# mother_card_09.net
KiCad netlist of a schematic drawn in EAGLE
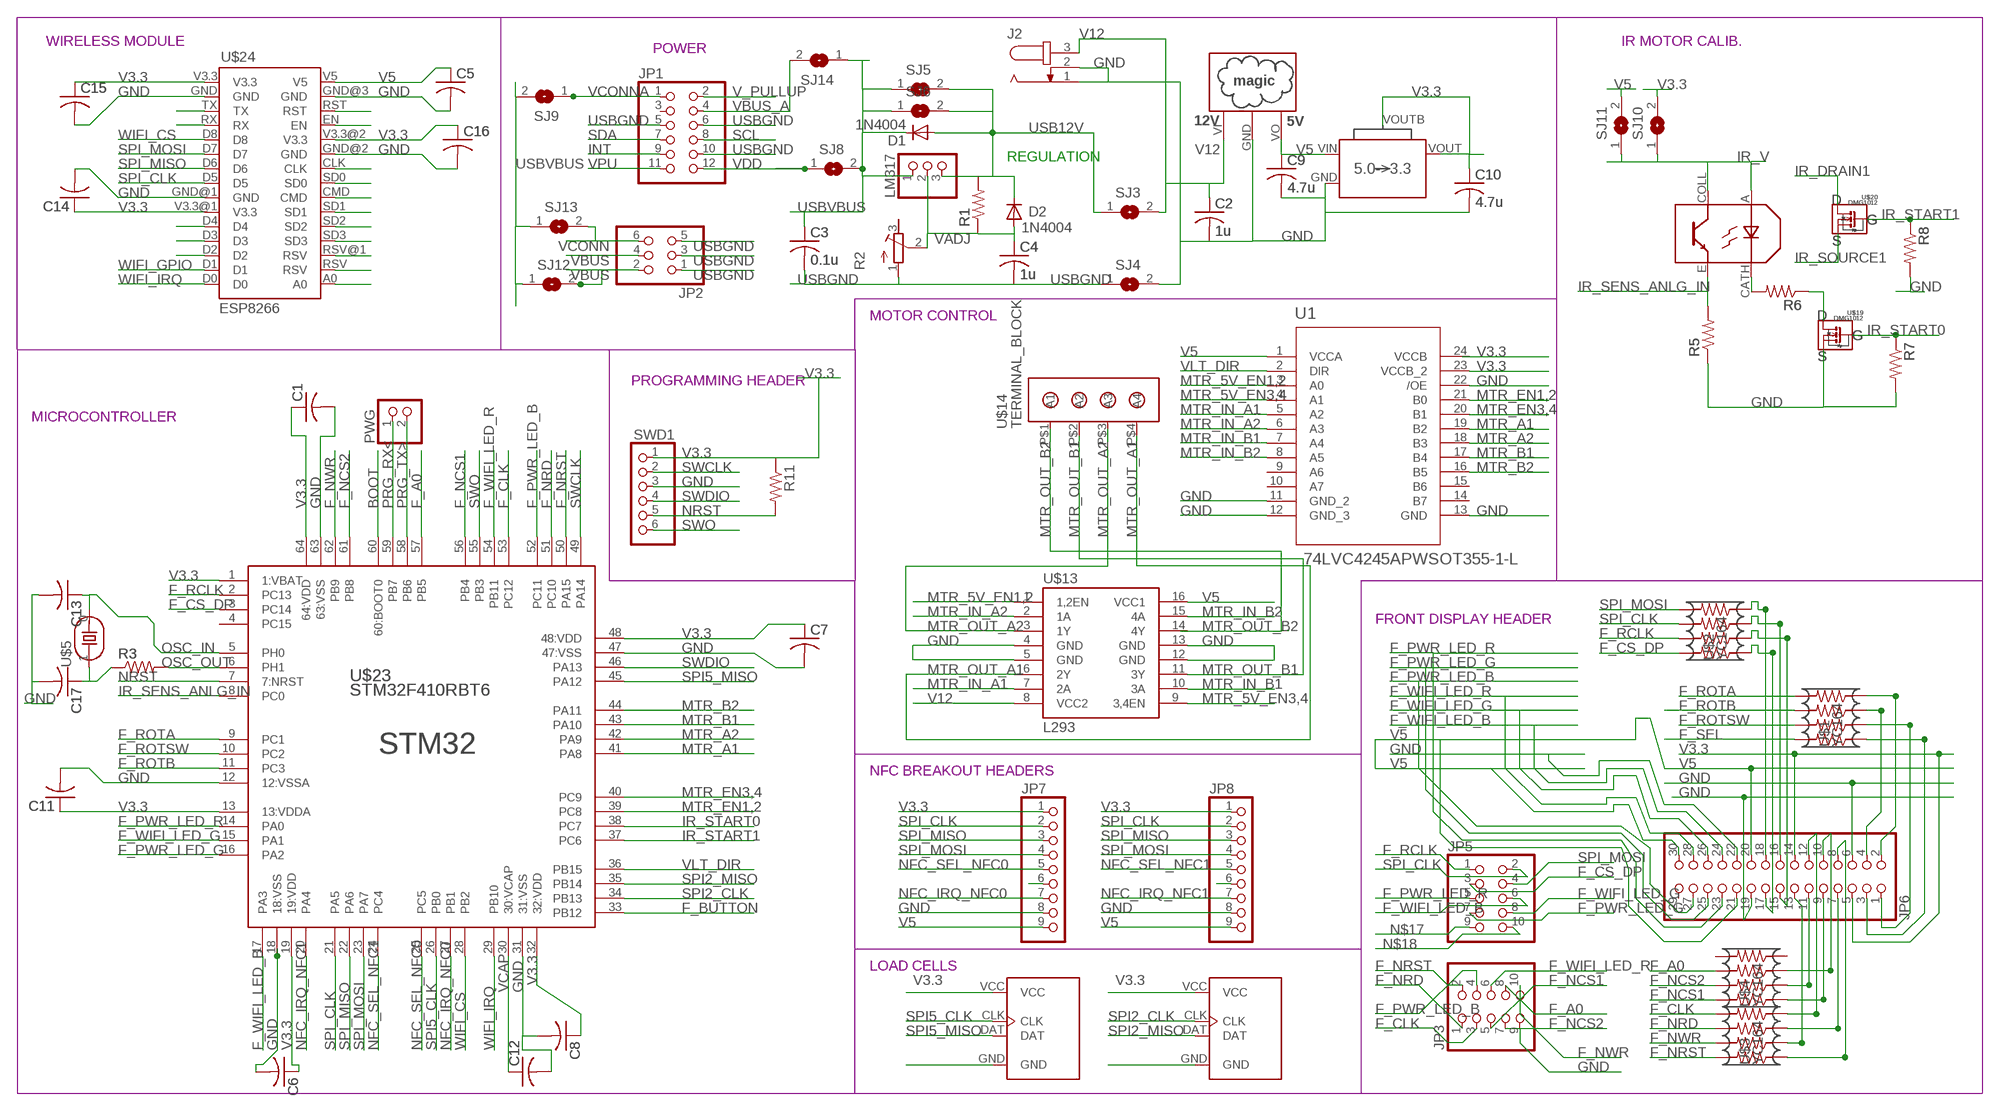
[diagram p0: schematic, sheet 1]

(export (version "E")
  (design (tool "Eeschema 10.0.6"))
  (components
    (comp (ref "C1")
      (value "C-USC0805")
      (footprint "eagle-import:C0805")
      (libsource (lib "eagle-import") (part "C-USC0805"))
    )
    (comp (ref "C2")
      (value "1u")
      (footprint "eagle-import:C0805")
      (libsource (lib "eagle-import") (part "C-USC0805"))
    )
    (comp (ref "C3")
      (value "0.1u")
      (footprint "eagle-import:C0805")
      (libsource (lib "eagle-import") (part "C-USC0805"))
    )
    (comp (ref "C4")
      (value "1u")
      (footprint "eagle-import:C0805")
      (libsource (lib "eagle-import") (part "C-USC0805"))
    )
    (comp (ref "C5")
      (value "C-USC0805")
      (footprint "eagle-import:C0805")
      (libsource (lib "eagle-import") (part "C-USC0805"))
    )
    (comp (ref "C6")
      (value "C-USC0805")
      (footprint "eagle-import:C0805")
      (libsource (lib "eagle-import") (part "C-USC0805"))
    )
    (comp (ref "C7")
      (value "C-USC0805")
      (footprint "eagle-import:C0805")
      (libsource (lib "eagle-import") (part "C-USC0805"))
    )
    (comp (ref "C8")
      (value "C-USC0805")
      (footprint "eagle-import:C0805")
      (libsource (lib "eagle-import") (part "C-USC0805"))
    )
    (comp (ref "C9")
      (value "4.7u")
      (footprint "eagle-import:C0805")
      (libsource (lib "eagle-import") (part "C-USC0805"))
    )
    (comp (ref "C10")
      (value "4.7u")
      (footprint "eagle-import:C0805")
      (libsource (lib "eagle-import") (part "C-USC0805"))
    )
    (comp (ref "C11")
      (value "C-USC0805")
      (footprint "eagle-import:C0805")
      (libsource (lib "eagle-import") (part "C-USC0805"))
    )
    (comp (ref "C12")
      (value "C-USC0805")
      (footprint "eagle-import:C0805")
      (libsource (lib "eagle-import") (part "C-USC0805"))
    )
    (comp (ref "C13")
      (value "C-USC0603")
      (footprint "eagle-import:C0603")
      (libsource (lib "eagle-import") (part "C-USC0603"))
    )
    (comp (ref "C14")
      (value "C-USC0805")
      (footprint "eagle-import:C0805")
      (libsource (lib "eagle-import") (part "C-USC0805"))
    )
    (comp (ref "C15")
      (value "C-USC0805")
      (footprint "eagle-import:C0805")
      (libsource (lib "eagle-import") (part "C-USC0805"))
    )
    (comp (ref "C16")
      (value "C-USC0805")
      (footprint "eagle-import:C0805")
      (libsource (lib "eagle-import") (part "C-USC0805"))
    )
    (comp (ref "C17")
      (value "C-USC0603")
      (footprint "eagle-import:C0603")
      (libsource (lib "eagle-import") (part "C-USC0603"))
    )
    (comp (ref "D1")
      (value "1N4004")
      (footprint "eagle-import:DO41-10")
      (libsource (lib "eagle-import") (part "1N4004"))
    )
    (comp (ref "D2")
      (value "1N4004")
      (footprint "eagle-import:DO41-10")
      (libsource (lib "eagle-import") (part "1N4004"))
    )
    (comp (ref "J2")
      (value "JACK-PLUG0")
      (footprint "eagle-import:SPC4077")
      (libsource (lib "eagle-import") (part "JACK-PLUG0"))
    )
    (comp (ref "JP1")
      (value "PINHD-2X6")
      (footprint "eagle-import:2X06")
      (libsource (lib "eagle-import") (part "PINHD-2X6"))
    )
    (comp (ref "JP2")
      (value "PINHD-2X3")
      (footprint "eagle-import:2X03")
      (libsource (lib "eagle-import") (part "PINHD-2X3"))
    )
    (comp (ref "JP3")
      (value "PINHD-2X5")
      (footprint "eagle-import:2X05")
      (libsource (lib "eagle-import") (part "PINHD-2X5"))
    )
    (comp (ref "JP5")
      (value "PINHD-2X5")
      (footprint "eagle-import:2X05")
      (libsource (lib "eagle-import") (part "PINHD-2X5"))
    )
    (comp (ref "JP6")
      (value "PINHD-2X15/SOCK")
      (footprint "eagle-import:2X15_SOCK")
      (libsource (lib "eagle-import") (part "PINHD-2X15/SOCK"))
    )
    (comp (ref "JP7")
      (value "PINHD-1X9/90")
      (footprint "eagle-import:1X09_90")
      (libsource (lib "eagle-import") (part "PINHD-1X9/90"))
    )
    (comp (ref "JP8")
      (value "PINHD-1X9/90")
      (footprint "eagle-import:1X09_90")
      (libsource (lib "eagle-import") (part "PINHD-1X9/90"))
    )
    (comp (ref "LM317")
      (value "PINHD-1X3")
      (footprint "eagle-import:1X03")
      (libsource (lib "eagle-import") (part "PINHD-1X3"))
    )
    (comp (ref "PWG")
      (value "PINHD-1X2")
      (footprint "eagle-import:1X02")
      (libsource (lib "eagle-import") (part "PINHD-1X2"))
    )
    (comp (ref "R1")
      (value "R-US_R0805")
      (footprint "eagle-import:R0805")
      (libsource (lib "eagle-import") (part "seniorDesign_R-US_R0805"))
    )
    (comp (ref "R2")
      (value "R-TRIMM64W")
      (footprint "eagle-import:RTRIM64W")
      (libsource (lib "eagle-import") (part "R-TRIMM64W"))
    )
    (comp (ref "R3")
      (value "R-US_R0805")
      (footprint "eagle-import:R0805")
      (libsource (lib "eagle-import") (part "seniorDesign_R-US_R0805"))
    )
    (comp (ref "R5")
      (value "R-US_R0805")
      (footprint "eagle-import:R0805")
      (libsource (lib "eagle-import") (part "seniorDesign_R-US_R0805"))
    )
    (comp (ref "R6")
      (value "R-US_R0805")
      (footprint "eagle-import:R0805")
      (libsource (lib "eagle-import") (part "seniorDesign_R-US_R0805"))
    )
    (comp (ref "R7")
      (value "R-US_R0805")
      (footprint "eagle-import:R0805")
      (libsource (lib "eagle-import") (part "seniorDesign_R-US_R0805"))
    )
    (comp (ref "R8")
      (value "R-US_R0805")
      (footprint "eagle-import:R0805")
      (libsource (lib "eagle-import") (part "seniorDesign_R-US_R0805"))
    )
    (comp (ref "R11")
      (value "R-US_R0805")
      (footprint "eagle-import:R0805")
      (libsource (lib "eagle-import") (part "R-US_R0805"))
    )
    (comp (ref "SJ3") (value "SJ") (footprint "eagle-import:SJ") (libsource (lib "eagle-import") (part "SJ")))
    (comp (ref "SJ4") (value "SJ") (footprint "eagle-import:SJ") (libsource (lib "eagle-import") (part "SJ")))
    (comp (ref "SJ5") (value "SJ") (footprint "eagle-import:SJ") (libsource (lib "eagle-import") (part "SJ")))
    (comp (ref "SJ6") (value "SJ") (footprint "eagle-import:SJ") (libsource (lib "eagle-import") (part "SJ")))
    (comp (ref "SJ8") (value "SJ") (footprint "eagle-import:SJ") (libsource (lib "eagle-import") (part "SJ")))
    (comp (ref "SJ9") (value "SJ") (footprint "eagle-import:SJ") (libsource (lib "eagle-import") (part "SJ")))
    (comp (ref "SJ10")
      (value "SJ")
      (footprint "eagle-import:SJ")
      (libsource (lib "eagle-import") (part "SJ"))
    )
    (comp (ref "SJ11")
      (value "SJ")
      (footprint "eagle-import:SJ")
      (libsource (lib "eagle-import") (part "SJ"))
    )
    (comp (ref "SJ12")
      (value "SJ")
      (footprint "eagle-import:SJ")
      (libsource (lib "eagle-import") (part "SJ"))
    )
    (comp (ref "SJ13")
      (value "SJ")
      (footprint "eagle-import:SJ")
      (libsource (lib "eagle-import") (part "SJ"))
    )
    (comp (ref "SJ14")
      (value "SJ")
      (footprint "eagle-import:SJ")
      (libsource (lib "eagle-import") (part "SJ"))
    )
    (comp (ref "SWD1")
      (value "PINHD-1X6")
      (footprint "eagle-import:1X06")
      (libsource (lib "eagle-import") (part "PINHD-1X6"))
    )
    (comp (ref "U$1")
      (value "YC164")
      (footprint "eagle-import:YC164")
      (libsource (lib "eagle-import") (part "YC164"))
    )
    (comp (ref "U$2")
      (value "YC164")
      (footprint "eagle-import:YC164")
      (libsource (lib "eagle-import") (part "YC164"))
    )
    (comp (ref "U$3")
      (value "YC164")
      (footprint "eagle-import:YC164")
      (libsource (lib "eagle-import") (part "YC164"))
    )
    (comp (ref "U$4")
      (value "YC164")
      (footprint "eagle-import:YC164")
      (libsource (lib "eagle-import") (part "YC164"))
    )
    (comp (ref "U$5")
      (value "HC-49S_9B")
      (footprint "eagle-import:HC-49S_9B")
      (libsource (lib "eagle-import") (part "HC-49S_9B"))
    )
    (comp (ref "U$13")
      (value "L293")
      (footprint "eagle-import:DIL16")
      (libsource (lib "eagle-import") (part "L293"))
    )
    (comp (ref "U$14")
      (value "TERMINAL_BLOCK")
      (footprint "eagle-import:1X4_BLOCK")
      (libsource (lib "eagle-import") (part "TERMINAL_BLOCK"))
    )
    (comp (ref "U$15")
      (value "AP2114H")
      (footprint "eagle-import:AP2114H")
      (libsource (lib "eagle-import") (part "AP2114H"))
    )
    (comp (ref "U$16")
      (value "OKI-78SR-W36")
      (footprint "eagle-import:SIP3")
      (libsource (lib "eagle-import") (part "OKI-78SR-W36"))
    )
    (comp (ref "U$18")
      (value "TCRT5000")
      (footprint "eagle-import:TCRT5000")
      (libsource (lib "eagle-import") (part "TCRT5000"))
    )
    (comp (ref "U$19")
      (value "DMG1012")
      (footprint "eagle-import:SOT323")
      (libsource (lib "eagle-import") (part "DMG1012"))
    )
    (comp (ref "U$20")
      (value "DMG1012")
      (footprint "eagle-import:SOT323")
      (libsource (lib "eagle-import") (part "DMG1012"))
    )
    (comp (ref "U$21")
      (value "HX711")
      (footprint "eagle-import:HX711")
      (libsource (lib "eagle-import") (part "HX711"))
    )
    (comp (ref "U$22")
      (value "HX711")
      (footprint "eagle-import:HX711")
      (libsource (lib "eagle-import") (part "HX711"))
    )
    (comp (ref "U$23")
      (value "STM32F410RBT6")
      (footprint "eagle-import:QFP50P1200X1200X160-64N")
      (libsource (lib "eagle-import") (part "STM32F410RBT6"))
    )
    (comp (ref "U$24")
      (value "ESP8266")
      (footprint "eagle-import:ESP8266")
      (libsource (lib "eagle-import") (part "ESP8266"))
    )
    (comp (ref "U1")
      (value "74LVC4245APWSOT355-1-L")
      (footprint "eagle-import:SOT355-1-L")
      (fields (field (name "MANUFACTURER_PART_NUMBER") "74LVC4245APW"))
      (libsource (lib "eagle-import") (part "74LVC4245APWSOT355-1-L"))
    )
  )
  (nets
    (net (code "1") (name "/BOOT") (class "Default")
      (node (ref "U$23") (pin "60") (pinfunction "60:BOOT0_60") (pintype "bidirectional"))
    )
    (net (code "2") (name "/F_A0") (class "Default")
      (node (ref "JP3") (pin "8") (pinfunction "8_8") (pintype "passive"))
      (node (ref "JP6") (pin "10") (pinfunction "10_10") (pintype "passive"))
      (node (ref "U$23") (pin "57") (pinfunction "PB5_57") (pintype "bidirectional"))
      (node (ref "U$4") (pin "P$3") (pinfunction "3_P$3") (pintype "passive"))
      (node (ref "U$4") (pin "P$33") (pinfunction "33_P$33") (pintype "passive"))
    )
    (net (code "3") (name "/F_BUTTON") (class "Default")
      (node (ref "U$23") (pin "33") (pinfunction "PB12_33") (pintype "bidirectional"))
    )
    (net (code "4") (name "/F_CLK") (class "Default")
      (node (ref "JP3") (pin "3") (pinfunction "3_3") (pintype "passive"))
      (node (ref "JP6") (pin "12") (pinfunction "12_12") (pintype "passive"))
      (node (ref "U$23") (pin "53") (pinfunction "PC12_53") (pintype "bidirectional"))
      (node (ref "U$3") (pin "P$4") (pinfunction "4_P$4") (pintype "passive"))
      (node (ref "U$3") (pin "P$44") (pinfunction "44_P$44") (pintype "passive"))
    )
    (net (code "5") (name "/F_CS_DP") (class "Default")
      (node (ref "JP5") (pin "3") (pinfunction "3_3") (pintype "passive"))
      (node (ref "U$2") (pin "P$1") (pinfunction "1_P$1") (pintype "passive"))
      (node (ref "U$23") (pin "3") (pinfunction "PC14_3") (pintype "bidirectional"))
    )
    (net (code "6") (name "/F_NCS1") (class "Default")
      (node (ref "JP3") (pin "5") (pinfunction "5_5") (pintype "passive"))
      (node (ref "JP6") (pin "9") (pinfunction "9_9") (pintype "passive"))
      (node (ref "U$23") (pin "56") (pinfunction "PB4_56") (pintype "bidirectional"))
      (node (ref "U$4") (pin "P$1") (pinfunction "1_P$1") (pintype "passive"))
      (node (ref "U$4") (pin "P$11") (pinfunction "11_P$11") (pintype "passive"))
    )
    (net (code "7") (name "/F_NCS2") (class "Default")
      (node (ref "JP3") (pin "7") (pinfunction "7_7") (pintype "passive"))
      (node (ref "JP6") (pin "11") (pinfunction "11_11") (pintype "passive"))
      (node (ref "U$23") (pin "61") (pinfunction "PB8_61") (pintype "bidirectional"))
      (node (ref "U$4") (pin "P$2") (pinfunction "2_P$2") (pintype "passive"))
      (node (ref "U$4") (pin "P$22") (pinfunction "22_P$22") (pintype "passive"))
    )
    (net (code "8") (name "/F_NRD") (class "Default")
      (node (ref "JP3") (pin "1") (pinfunction "1_1") (pintype "passive"))
      (node (ref "JP6") (pin "7") (pinfunction "7_7") (pintype "passive"))
      (node (ref "U$23") (pin "51") (pinfunction "PC10_51") (pintype "bidirectional"))
      (node (ref "U$3") (pin "P$3") (pinfunction "3_P$3") (pintype "passive"))
      (node (ref "U$3") (pin "P$33") (pinfunction "33_P$33") (pintype "passive"))
    )
    (net (code "9") (name "/F_NRST") (class "Default")
      (node (ref "JP3") (pin "2") (pinfunction "2_2") (pintype "passive"))
      (node (ref "JP6") (pin "8") (pinfunction "8_8") (pintype "passive"))
      (node (ref "U$23") (pin "50") (pinfunction "PA15_50") (pintype "bidirectional"))
      (node (ref "U$3") (pin "P$1") (pinfunction "1_P$1") (pintype "passive"))
      (node (ref "U$3") (pin "P$11") (pinfunction "11_P$11") (pintype "passive"))
    )
    (net (code "10") (name "/F_NWR") (class "Default")
      (node (ref "JP3") (pin "10") (pinfunction "10_10") (pintype "passive"))
      (node (ref "JP6") (pin "13") (pinfunction "13_13") (pintype "passive"))
      (node (ref "U$23") (pin "62") (pinfunction "PB9_62") (pintype "bidirectional"))
      (node (ref "U$3") (pin "P$2") (pinfunction "2_P$2") (pintype "passive"))
      (node (ref "U$3") (pin "P$22") (pinfunction "22_P$22") (pintype "passive"))
    )
    (net (code "11") (name "/F_PWR_LED_B") (class "Default")
      (node (ref "JP3") (pin "4") (pinfunction "4_4") (pintype "passive"))
      (node (ref "JP6") (pin "27") (pinfunction "27_27") (pintype "passive"))
      (node (ref "U$23") (pin "52") (pinfunction "PC11_52") (pintype "bidirectional"))
    )
    (net (code "12") (name "/F_PWR_LED_G") (class "Default")
      (node (ref "JP5") (pin "7") (pinfunction "7_7") (pintype "passive"))
      (node (ref "JP6") (pin "25") (pinfunction "25_25") (pintype "passive"))
      (node (ref "U$23") (pin "16") (pinfunction "PA2_16") (pintype "bidirectional"))
    )
    (net (code "13") (name "/F_PWR_LED_R") (class "Default")
      (node (ref "JP5") (pin "5") (pinfunction "5_5") (pintype "passive"))
      (node (ref "JP6") (pin "23") (pinfunction "23_23") (pintype "passive"))
      (node (ref "U$23") (pin "14") (pinfunction "PA0_14") (pintype "bidirectional"))
    )
    (net (code "14") (name "/F_RCLK") (class "Default")
      (node (ref "JP5") (pin "1") (pinfunction "1_1") (pintype "passive"))
      (node (ref "U$2") (pin "P$2") (pinfunction "2_P$2") (pintype "passive"))
      (node (ref "U$23") (pin "2") (pinfunction "PC13_2") (pintype "bidirectional"))
    )
    (net (code "15") (name "/F_ROTA") (class "Default")
      (node (ref "U$1") (pin "P$4") (pinfunction "4_P$4") (pintype "passive"))
      (node (ref "U$23") (pin "9") (pinfunction "PC1_9") (pintype "bidirectional"))
    )
    (net (code "16") (name "/F_ROTB") (class "Default")
      (node (ref "JP6") (pin "4") (pinfunction "4_4") (pintype "passive"))
      (node (ref "U$1") (pin "P$3") (pinfunction "3_P$3") (pintype "passive"))
      (node (ref "U$1") (pin "P$33") (pinfunction "33_P$33") (pintype "passive"))
      (node (ref "U$23") (pin "11") (pinfunction "PC3_11") (pintype "bidirectional"))
    )
    (net (code "17") (name "/F_ROTSW") (class "Default")
      (node (ref "U$1") (pin "P$2") (pinfunction "2_P$2") (pintype "passive"))
      (node (ref "U$23") (pin "10") (pinfunction "PC2_10") (pintype "bidirectional"))
    )
    (net (code "18") (name "/F_SEL") (class "Default")
      (node (ref "U$1") (pin "P$1") (pinfunction "1_P$1") (pintype "passive"))
    )
    (net (code "19") (name "/F_WIFI_LED_B") (class "Default")
      (node (ref "JP5") (pin "6") (pinfunction "6_6") (pintype "passive"))
      (node (ref "JP6") (pin "24") (pinfunction "24_24") (pintype "passive"))
      (node (ref "U$23") (pin "17") (pinfunction "PA3_17") (pintype "bidirectional"))
    )
    (net (code "20") (name "/F_WIFI_LED_G") (class "Default")
      (node (ref "JP5") (pin "8") (pinfunction "8_8") (pintype "passive"))
      (node (ref "JP6") (pin "26") (pinfunction "26_26") (pintype "passive"))
      (node (ref "U$23") (pin "15") (pinfunction "PA1_15") (pintype "bidirectional"))
    )
    (net (code "21") (name "/F_WIFI_LED_R") (class "Default")
      (node (ref "JP3") (pin "6") (pinfunction "6_6") (pintype "passive"))
      (node (ref "JP6") (pin "28") (pinfunction "28_28") (pintype "passive"))
      (node (ref "U$23") (pin "54") (pinfunction "PB11_54") (pintype "bidirectional"))
    )
    (net (code "22") (name "/GND") (class "Default")
      (node (ref "C1") (pin "2") (pinfunction "2_2") (pintype "passive"))
      (node (ref "C10") (pin "2") (pinfunction "2_2") (pintype "passive"))
      (node (ref "C11") (pin "2") (pinfunction "2_2") (pintype "passive"))
      (node (ref "C12") (pin "2") (pinfunction "2_2") (pintype "passive"))
      (node (ref "C13") (pin "2") (pinfunction "2_2") (pintype "passive"))
      (node (ref "C14") (pin "2") (pinfunction "2_2") (pintype "passive"))
      (node (ref "C15") (pin "2") (pinfunction "2_2") (pintype "passive"))
      (node (ref "C16") (pin "2") (pinfunction "2_2") (pintype "passive"))
      (node (ref "C17") (pin "2") (pinfunction "2_2") (pintype "passive"))
      (node (ref "C2") (pin "2") (pinfunction "2_2") (pintype "passive"))
      (node (ref "C5") (pin "2") (pinfunction "2_2") (pintype "passive"))
      (node (ref "C6") (pin "2") (pinfunction "2_2") (pintype "passive"))
      (node (ref "C7") (pin "2") (pinfunction "2_2") (pintype "passive"))
      (node (ref "C8") (pin "2") (pinfunction "2_2") (pintype "passive"))
      (node (ref "C9") (pin "2") (pinfunction "2_2") (pintype "passive"))
      (node (ref "J2") (pin "1") (pinfunction "1_1") (pintype "passive"))
      (node (ref "J2") (pin "2") (pinfunction "2_2") (pintype "passive"))
      (node (ref "JP3") (pin "9") (pinfunction "9_9") (pintype "passive"))
      (node (ref "JP6") (pin "19") (pinfunction "19_19") (pintype "passive"))
      (node (ref "JP6") (pin "22") (pinfunction "22_22") (pintype "passive"))
      (node (ref "JP6") (pin "6") (pinfunction "6_6") (pintype "passive"))
      (node (ref "JP7") (pin "8") (pinfunction "8_8") (pintype "passive"))
      (node (ref "JP8") (pin "8") (pinfunction "8_8") (pintype "passive"))
      (node (ref "R5") (pin "1") (pinfunction "1_1") (pintype "passive"))
      (node (ref "R7") (pin "2") (pinfunction "2_2") (pintype "passive"))
      (node (ref "R8") (pin "2") (pinfunction "2_2") (pintype "passive"))
      (node (ref "SJ4") (pin "2") (pinfunction "2_2") (pintype "passive"))
      (node (ref "SWD1") (pin "3") (pinfunction "3_3") (pintype "passive"))
      (node (ref "U$13") (pin "12") (pinfunction "GND_12") (pintype "bidirectional"))
      (node (ref "U$13") (pin "13") (pinfunction "GND_13") (pintype "bidirectional"))
      (node (ref "U$13") (pin "4") (pinfunction "GND_4") (pintype "bidirectional"))
      (node (ref "U$13") (pin "5") (pinfunction "GND_5") (pintype "bidirectional"))
      (node (ref "U$15") (pin "GND") (pinfunction "GND_GND") (pintype "power_in"))
      (node (ref "U$16") (pin "GND") (pinfunction "P$2_GND") (pintype "power_in"))
      (node (ref "U$19") (pin "S") (pinfunction "S_S") (pintype "bidirectional"))
      (node (ref "U$21") (pin "GND") (pinfunction "GND_GND") (pintype "power_in"))
      (node (ref "U$22") (pin "GND") (pinfunction "GND_GND") (pintype "power_in"))
      (node (ref "U$23") (pin "12") (pinfunction "12:VSSA_12") (pintype "bidirectional"))
      (node (ref "U$23") (pin "18") (pinfunction "18:VSS_18") (pintype "bidirectional"))
      (node (ref "U$23") (pin "31") (pinfunction "31:VSS_31") (pintype "bidirectional"))
      (node (ref "U$23") (pin "47") (pinfunction "47:VSS_47") (pintype "bidirectional"))
      (node (ref "U$23") (pin "63") (pinfunction "63:VSS_63") (pintype "bidirectional"))
      (node (ref "U$24") (pin "GND") (pinfunction "GND_GND") (pintype "bidirectional"))
      (node (ref "U$24") (pin "GND@1") (pinfunction "GND_GND@1") (pintype "bidirectional"))
      (node (ref "U$24") (pin "GND@2") (pinfunction "GND_GND@2") (pintype "bidirectional"))
      (node (ref "U$24") (pin "GND@3") (pinfunction "GND_GND@3") (pintype "bidirectional"))
      (node (ref "U1") (pin "11") (pinfunction "GND_2_11") (pintype "power_in"))
      (node (ref "U1") (pin "12") (pinfunction "GND_3_12") (pintype "power_in"))
      (node (ref "U1") (pin "13") (pinfunction "GND_13") (pintype "power_in"))
      (node (ref "U1") (pin "22") (pinfunction "/OE_22") (pintype "input"))
    )
    (net (code "23") (name "/INT") (class "Default")
      (node (ref "JP1") (pin "9") (pinfunction "9_9") (pintype "passive"))
    )
    (net (code "24") (name "/IR_DRAIN1") (class "Default")
      (node (ref "U$20") (pin "D") (pinfunction "D_D") (pintype "bidirectional"))
    )
    (net (code "25") (name "/IR_SENS_ANLG_IN") (class "Default")
      (node (ref "R5") (pin "2") (pinfunction "2_2") (pintype "passive"))
      (node (ref "U$18") (pin "E") (pinfunction "E_E") (pintype "bidirectional"))
      (node (ref "U$23") (pin "8") (pinfunction "PC0_8") (pintype "bidirectional"))
    )
    (net (code "26") (name "/IR_SOURCE1") (class "Default")
      (node (ref "U$20") (pin "S") (pinfunction "S_S") (pintype "bidirectional"))
    )
    (net (code "27") (name "/IR_START0") (class "Default")
      (node (ref "R7") (pin "1") (pinfunction "1_1") (pintype "passive"))
      (node (ref "U$19") (pin "G") (pinfunction "G_G") (pintype "bidirectional"))
      (node (ref "U$23") (pin "38") (pinfunction "PC7_38") (pintype "bidirectional"))
    )
    (net (code "28") (name "/IR_START1") (class "Default")
      (node (ref "R8") (pin "1") (pinfunction "1_1") (pintype "passive"))
      (node (ref "U$20") (pin "G") (pinfunction "G_G") (pintype "bidirectional"))
      (node (ref "U$23") (pin "37") (pinfunction "PC6_37") (pintype "bidirectional"))
    )
    (net (code "29") (name "/IR_V") (class "Default")
      (node (ref "SJ10") (pin "1") (pinfunction "1_1") (pintype "passive"))
      (node (ref "SJ11") (pin "1") (pinfunction "1_1") (pintype "passive"))
      (node (ref "U$18") (pin "A") (pinfunction "A_A") (pintype "bidirectional"))
      (node (ref "U$18") (pin "COLL") (pinfunction "COLL_COLL") (pintype "bidirectional"))
    )
    (net (code "30") (name "/MTR_5V_EN1,2") (class "Default")
      (node (ref "U$13") (pin "1") (pinfunction "1,2EN_1") (pintype "bidirectional"))
      (node (ref "U1") (pin "3") (pinfunction "A0_3") (pintype "bidirectional"))
    )
    (net (code "31") (name "/MTR_5V_EN3,4") (class "Default")
      (node (ref "U$13") (pin "9") (pinfunction "3,4EN_9") (pintype "bidirectional"))
      (node (ref "U1") (pin "4") (pinfunction "A1_4") (pintype "bidirectional"))
    )
    (net (code "32") (name "/MTR_A1") (class "Default")
      (node (ref "U$23") (pin "41") (pinfunction "PA8_41") (pintype "bidirectional"))
      (node (ref "U1") (pin "19") (pinfunction "B2_19") (pintype "bidirectional"))
    )
    (net (code "33") (name "/MTR_A2") (class "Default")
      (node (ref "U$23") (pin "42") (pinfunction "PA9_42") (pintype "bidirectional"))
      (node (ref "U1") (pin "18") (pinfunction "B3_18") (pintype "bidirectional"))
    )
    (net (code "34") (name "/MTR_B1") (class "Default")
      (node (ref "U$23") (pin "43") (pinfunction "PA10_43") (pintype "bidirectional"))
      (node (ref "U1") (pin "17") (pinfunction "B4_17") (pintype "bidirectional"))
    )
    (net (code "35") (name "/MTR_B2") (class "Default")
      (node (ref "U$23") (pin "44") (pinfunction "PA11_44") (pintype "bidirectional"))
      (node (ref "U1") (pin "16") (pinfunction "B5_16") (pintype "bidirectional"))
    )
    (net (code "36") (name "/MTR_EN1,2") (class "Default")
      (node (ref "U$23") (pin "39") (pinfunction "PC8_39") (pintype "bidirectional"))
      (node (ref "U1") (pin "21") (pinfunction "B0_21") (pintype "bidirectional"))
    )
    (net (code "37") (name "/MTR_EN3,4") (class "Default")
      (node (ref "U$23") (pin "40") (pinfunction "PC9_40") (pintype "bidirectional"))
      (node (ref "U1") (pin "20") (pinfunction "B1_20") (pintype "bidirectional"))
    )
    (net (code "38") (name "/MTR_IN_A1") (class "Default")
      (node (ref "U$13") (pin "7") (pinfunction "2A_7") (pintype "bidirectional"))
      (node (ref "U1") (pin "5") (pinfunction "A2_5") (pintype "bidirectional"))
    )
    (net (code "39") (name "/MTR_IN_A2") (class "Default")
      (node (ref "U$13") (pin "2") (pinfunction "1A_2") (pintype "bidirectional"))
      (node (ref "U1") (pin "6") (pinfunction "A3_6") (pintype "bidirectional"))
    )
    (net (code "40") (name "/MTR_IN_B1") (class "Default")
      (node (ref "U$13") (pin "10") (pinfunction "3A_10") (pintype "bidirectional"))
      (node (ref "U1") (pin "7") (pinfunction "A4_7") (pintype "bidirectional"))
    )
    (net (code "41") (name "/MTR_IN_B2") (class "Default")
      (node (ref "U$13") (pin "15") (pinfunction "4A_15") (pintype "bidirectional"))
      (node (ref "U1") (pin "8") (pinfunction "A5_8") (pintype "bidirectional"))
    )
    (net (code "42") (name "/MTR_OUT_A1") (class "Default")
      (node (ref "U$13") (pin "6") (pinfunction "2Y_6") (pintype "bidirectional"))
      (node (ref "U$14") (pin "P$4") (pinfunction "A4_P$4") (pintype "bidirectional"))
    )
    (net (code "43") (name "/MTR_OUT_A2") (class "Default")
      (node (ref "U$13") (pin "3") (pinfunction "1Y_3") (pintype "bidirectional"))
      (node (ref "U$14") (pin "P$3") (pinfunction "A3_P$3") (pintype "bidirectional"))
    )
    (net (code "44") (name "/MTR_OUT_B1") (class "Default")
      (node (ref "U$13") (pin "11") (pinfunction "3Y_11") (pintype "bidirectional"))
      (node (ref "U$14") (pin "P$2") (pinfunction "A2_P$2") (pintype "bidirectional"))
    )
    (net (code "45") (name "/MTR_OUT_B2") (class "Default")
      (node (ref "U$13") (pin "14") (pinfunction "4Y_14") (pintype "bidirectional"))
      (node (ref "U$14") (pin "P$1") (pinfunction "A1_P$1") (pintype "bidirectional"))
    )
    (net (code "46") (name "/N$17") (class "Default")
      (node (ref "JP5") (pin "9") (pinfunction "9_9") (pintype "passive"))
    )
    (net (code "47") (name "/N$18") (class "Default")
      (node (ref "JP5") (pin "10") (pinfunction "10_10") (pintype "passive"))
    )
    (net (code "48") (name "/NFC_IRQ_NFC0") (class "Default")
      (node (ref "JP7") (pin "7") (pinfunction "7_7") (pintype "passive"))
      (node (ref "U$23") (pin "27") (pinfunction "PB1_27") (pintype "bidirectional"))
    )
    (net (code "49") (name "/NFC_IRQ_NFC1") (class "Default")
      (node (ref "JP8") (pin "7") (pinfunction "7_7") (pintype "passive"))
      (node (ref "U$23") (pin "20") (pinfunction "PA4_20") (pintype "bidirectional"))
    )
    (net (code "50") (name "/NFC_SEL_NFC0") (class "Default")
      (node (ref "JP7") (pin "5") (pinfunction "5_5") (pintype "passive"))
      (node (ref "U$23") (pin "25") (pinfunction "PC5_25") (pintype "bidirectional"))
    )
    (net (code "51") (name "/NFC_SEL_NFC1") (class "Default")
      (node (ref "JP8") (pin "5") (pinfunction "5_5") (pintype "passive"))
      (node (ref "U$23") (pin "24") (pinfunction "PC4_24") (pintype "bidirectional"))
    )
    (net (code "52") (name "/NRST") (class "Default")
      (node (ref "R11") (pin "2") (pinfunction "2_2") (pintype "passive"))
      (node (ref "SWD1") (pin "5") (pinfunction "5_5") (pintype "passive"))
      (node (ref "U$23") (pin "7") (pinfunction "7:NRST_7") (pintype "bidirectional"))
    )
    (net (code "53") (name "/OSC_IN") (class "Default")
      (node (ref "C13") (pin "1") (pinfunction "1_1") (pintype "passive"))
      (node (ref "U$23") (pin "5") (pinfunction "PH0_5") (pintype "bidirectional"))
      (node (ref "U$5") (pin "0") (pinfunction "P$1_0") (pintype "bidirectional"))
    )
    (net (code "54") (name "/OSC_OUT") (class "Default")
      (node (ref "C17") (pin "1") (pinfunction "1_1") (pintype "passive"))
      (node (ref "R3") (pin "1") (pinfunction "1_1") (pintype "passive"))
      (node (ref "U$5") (pin "1") (pinfunction "P$2_1") (pintype "bidirectional"))
    )
    (net (code "55") (name "/PRG_RX<") (class "Default")
      (node (ref "PWG") (pin "1") (pinfunction "1_1") (pintype "passive"))
      (node (ref "U$23") (pin "59") (pinfunction "PB7_59") (pintype "bidirectional"))
    )
    (net (code "56") (name "/PRG_TX>") (class "Default")
      (node (ref "PWG") (pin "2") (pinfunction "2_2") (pintype "passive"))
      (node (ref "U$23") (pin "58") (pinfunction "PB6_58") (pintype "bidirectional"))
    )
    (net (code "57") (name "/SCL") (class "Default")
      (node (ref "JP1") (pin "8") (pinfunction "8_8") (pintype "passive"))
    )
    (net (code "58") (name "/SDA") (class "Default")
      (node (ref "JP1") (pin "7") (pinfunction "7_7") (pintype "passive"))
    )
    (net (code "59") (name "/SPI2_CLK") (class "Default")
      (node (ref "U$22") (pin "CLK") (pinfunction "CLK_CLK") (pintype "bidirectional"))
      (node (ref "U$23") (pin "34") (pinfunction "PB13_34") (pintype "bidirectional"))
    )
    (net (code "60") (name "/SPI2_MISO") (class "Default")
      (node (ref "U$22") (pin "DAT") (pinfunction "DAT_DAT") (pintype "bidirectional"))
      (node (ref "U$23") (pin "35") (pinfunction "PB14_35") (pintype "bidirectional"))
    )
    (net (code "61") (name "/SPI5_CLK") (class "Default")
      (node (ref "U$21") (pin "CLK") (pinfunction "CLK_CLK") (pintype "bidirectional"))
      (node (ref "U$23") (pin "26") (pinfunction "PB0_26") (pintype "bidirectional"))
    )
    (net (code "62") (name "/SPI5_MISO") (class "Default")
      (node (ref "U$21") (pin "DAT") (pinfunction "DAT_DAT") (pintype "bidirectional"))
      (node (ref "U$23") (pin "45") (pinfunction "PA12_45") (pintype "bidirectional"))
    )
    (net (code "63") (name "/SPI_CLK") (class "Default")
      (node (ref "JP5") (pin "2") (pinfunction "2_2") (pintype "passive"))
      (node (ref "JP7") (pin "2") (pinfunction "2_2") (pintype "passive"))
      (node (ref "JP8") (pin "2") (pinfunction "2_2") (pintype "passive"))
      (node (ref "U$2") (pin "P$3") (pinfunction "3_P$3") (pintype "passive"))
      (node (ref "U$23") (pin "21") (pinfunction "PA5_21") (pintype "bidirectional"))
      (node (ref "U$24") (pin "D5") (pinfunction "D5_D5") (pintype "bidirectional"))
    )
    (net (code "64") (name "/SPI_MISO") (class "Default")
      (node (ref "JP7") (pin "3") (pinfunction "3_3") (pintype "passive"))
      (node (ref "JP8") (pin "3") (pinfunction "3_3") (pintype "passive"))
      (node (ref "U$23") (pin "22") (pinfunction "PA6_22") (pintype "bidirectional"))
      (node (ref "U$24") (pin "D6") (pinfunction "D6_D6") (pintype "bidirectional"))
    )
    (net (code "65") (name "/SPI_MOSI") (class "Default")
      (node (ref "JP5") (pin "4") (pinfunction "4_4") (pintype "passive"))
      (node (ref "JP7") (pin "4") (pinfunction "4_4") (pintype "passive"))
      (node (ref "JP8") (pin "4") (pinfunction "4_4") (pintype "passive"))
      (node (ref "U$2") (pin "P$4") (pinfunction "4_P$4") (pintype "passive"))
      (node (ref "U$23") (pin "23") (pinfunction "PA7_23") (pintype "bidirectional"))
      (node (ref "U$24") (pin "D7") (pinfunction "D7_D7") (pintype "bidirectional"))
    )
    (net (code "66") (name "/SWCLK") (class "Default")
      (node (ref "SWD1") (pin "2") (pinfunction "2_2") (pintype "passive"))
      (node (ref "U$23") (pin "49") (pinfunction "PA14_49") (pintype "bidirectional"))
    )
    (net (code "67") (name "/SWDIO") (class "Default")
      (node (ref "SWD1") (pin "4") (pinfunction "4_4") (pintype "passive"))
      (node (ref "U$23") (pin "46") (pinfunction "PA13_46") (pintype "bidirectional"))
    )
    (net (code "68") (name "/SWO") (class "Default")
      (node (ref "SWD1") (pin "6") (pinfunction "6_6") (pintype "passive"))
      (node (ref "U$23") (pin "55") (pinfunction "PB3_55") (pintype "bidirectional"))
    )
    (net (code "69") (name "/USB12V") (class "Default")
      (node (ref "D1") (pin "A") (pinfunction "A_A") (pintype "passive"))
      (node (ref "D2") (pin "C") (pinfunction "C_C") (pintype "passive"))
      (node (ref "LM317") (pin "3") (pinfunction "3_3") (pintype "passive"))
      (node (ref "R1") (pin "2") (pinfunction "2_2") (pintype "passive"))
      (node (ref "SJ3") (pin "1") (pinfunction "1_1") (pintype "passive"))
      (node (ref "SJ5") (pin "2") (pinfunction "2_2") (pintype "passive"))
      (node (ref "SJ6") (pin "2") (pinfunction "2_2") (pintype "passive"))
    )
    (net (code "70") (name "/USBGND") (class "Default")
      (node (ref "C3") (pin "2") (pinfunction "2_2") (pintype "passive"))
      (node (ref "C4") (pin "2") (pinfunction "2_2") (pintype "passive"))
      (node (ref "JP1") (pin "10") (pinfunction "10_10") (pintype "passive"))
      (node (ref "JP1") (pin "5") (pinfunction "5_5") (pintype "passive"))
      (node (ref "JP1") (pin "6") (pinfunction "6_6") (pintype "passive"))
      (node (ref "JP2") (pin "1") (pinfunction "1_1") (pintype "passive"))
      (node (ref "JP2") (pin "3") (pinfunction "3_3") (pintype "passive"))
      (node (ref "JP2") (pin "5") (pinfunction "5_5") (pintype "passive"))
      (node (ref "R2") (pin "1") (pinfunction "A_1") (pintype "passive"))
      (node (ref "SJ4") (pin "1") (pinfunction "1_1") (pintype "passive"))
    )
    (net (code "71") (name "/USBVBUS") (class "Default")
      (node (ref "C3") (pin "1") (pinfunction "1_1") (pintype "passive"))
      (node (ref "D1") (pin "C") (pinfunction "C_C") (pintype "passive"))
      (node (ref "LM317") (pin "1") (pinfunction "1_1") (pintype "passive"))
      (node (ref "SJ12") (pin "1") (pinfunction "1_1") (pintype "passive"))
      (node (ref "SJ13") (pin "1") (pinfunction "1_1") (pintype "passive"))
      (node (ref "SJ14") (pin "1") (pinfunction "1_1") (pintype "passive"))
      (node (ref "SJ5") (pin "1") (pinfunction "1_1") (pintype "passive"))
      (node (ref "SJ6") (pin "1") (pinfunction "1_1") (pintype "passive"))
      (node (ref "SJ8") (pin "2") (pinfunction "2_2") (pintype "passive"))
      (node (ref "SJ9") (pin "2") (pinfunction "2_2") (pintype "passive"))
    )
    (net (code "72") (name "/V3.3") (class "Default")
      (node (ref "C1") (pin "1") (pinfunction "1_1") (pintype "passive"))
      (node (ref "C10") (pin "1") (pinfunction "1_1") (pintype "passive"))
      (node (ref "C11") (pin "1") (pinfunction "1_1") (pintype "passive"))
      (node (ref "C14") (pin "1") (pinfunction "1_1") (pintype "passive"))
      (node (ref "C15") (pin "1") (pinfunction "1_1") (pintype "passive"))
      (node (ref "C16") (pin "1") (pinfunction "1_1") (pintype "passive"))
      (node (ref "C6") (pin "1") (pinfunction "1_1") (pintype "passive"))
      (node (ref "C7") (pin "1") (pinfunction "1_1") (pintype "passive"))
      (node (ref "C8") (pin "1") (pinfunction "1_1") (pintype "passive"))
      (node (ref "JP6") (pin "14") (pinfunction "14_14") (pintype "passive"))
      (node (ref "JP6") (pin "5") (pinfunction "5_5") (pintype "passive"))
      (node (ref "JP7") (pin "1") (pinfunction "1_1") (pintype "passive"))
      (node (ref "JP8") (pin "1") (pinfunction "1_1") (pintype "passive"))
      (node (ref "R11") (pin "1") (pinfunction "1_1") (pintype "passive"))
      (node (ref "SJ10") (pin "2") (pinfunction "2_2") (pintype "passive"))
      (node (ref "SWD1") (pin "1") (pinfunction "1_1") (pintype "passive"))
      (node (ref "U$15") (pin "VOUT") (pinfunction "VO_VOUT") (pintype "output"))
      (node (ref "U$15") (pin "VOUTB") (pinfunction "BODY_VOUTB") (pintype "open_collector"))
      (node (ref "U$21") (pin "VCC") (pinfunction "VCC_VCC") (pintype "power_in"))
      (node (ref "U$22") (pin "VCC") (pinfunction "VCC_VCC") (pintype "power_in"))
      (node (ref "U$23") (pin "1") (pinfunction "1:VBAT_1") (pintype "bidirectional"))
      (node (ref "U$23") (pin "13") (pinfunction "13:VDDA_13") (pintype "bidirectional"))
      (node (ref "U$23") (pin "19") (pinfunction "19:VDD_19") (pintype "bidirectional"))
      (node (ref "U$23") (pin "32") (pinfunction "32:VDD_32") (pintype "bidirectional"))
      (node (ref "U$23") (pin "48") (pinfunction "48:VDD_48") (pintype "bidirectional"))
      (node (ref "U$23") (pin "64") (pinfunction "64:VDD_64") (pintype "bidirectional"))
      (node (ref "U$24") (pin "V3.3") (pinfunction "V3.3_V3.3") (pintype "bidirectional"))
      (node (ref "U$24") (pin "V3.3@1") (pinfunction "V3.3_V3.3@1") (pintype "bidirectional"))
      (node (ref "U$24") (pin "V3.3@2") (pinfunction "V3.3_V3.3@2") (pintype "bidirectional"))
      (node (ref "U1") (pin "23") (pinfunction "VCCB_2_23") (pintype "power_in"))
      (node (ref "U1") (pin "24") (pinfunction "VCCB_24") (pintype "power_in"))
    )
    (net (code "73") (name "/V5") (class "Default")
      (node (ref "C5") (pin "1") (pinfunction "1_1") (pintype "passive"))
      (node (ref "C9") (pin "1") (pinfunction "1_1") (pintype "passive"))
      (node (ref "JP6") (pin "20") (pinfunction "20_20") (pintype "passive"))
      (node (ref "JP6") (pin "21") (pinfunction "21_21") (pintype "passive"))
      (node (ref "JP6") (pin "30") (pinfunction "30_30") (pintype "passive"))
      (node (ref "JP7") (pin "9") (pinfunction "9_9") (pintype "passive"))
      (node (ref "JP8") (pin "9") (pinfunction "9_9") (pintype "passive"))
      (node (ref "SJ11") (pin "2") (pinfunction "2_2") (pintype "passive"))
      (node (ref "U$13") (pin "16") (pinfunction "VCC1_16") (pintype "bidirectional"))
      (node (ref "U$15") (pin "VIN") (pinfunction "VI_VIN") (pintype "input"))
      (node (ref "U$16") (pin "VO") (pinfunction "P$3_VO") (pintype "output"))
      (node (ref "U$24") (pin "V5") (pinfunction "V5_V5") (pintype "bidirectional"))
      (node (ref "U1") (pin "1") (pinfunction "VCCA_1") (pintype "power_in"))
    )
    (net (code "74") (name "/V12") (class "Default")
      (node (ref "C2") (pin "1") (pinfunction "1_1") (pintype "passive"))
      (node (ref "J2") (pin "3") (pinfunction "3_3") (pintype "passive"))
      (node (ref "SJ3") (pin "2") (pinfunction "2_2") (pintype "passive"))
      (node (ref "U$13") (pin "8") (pinfunction "VCC2_8") (pintype "bidirectional"))
      (node (ref "U$16") (pin "VI") (pinfunction "P$1_VI") (pintype "input"))
    )
    (net (code "75") (name "/VADJ") (class "Default")
      (node (ref "C4") (pin "1") (pinfunction "1_1") (pintype "passive"))
      (node (ref "D2") (pin "A") (pinfunction "A_A") (pintype "passive"))
      (node (ref "LM317") (pin "2") (pinfunction "2_2") (pintype "passive"))
      (node (ref "R1") (pin "1") (pinfunction "1_1") (pintype "passive"))
      (node (ref "R2") (pin "2") (pinfunction "S_2") (pintype "passive"))
    )
    (net (code "76") (name "/VBUS") (class "Default")
      (node (ref "JP2") (pin "2") (pinfunction "2_2") (pintype "passive"))
      (node (ref "JP2") (pin "4") (pinfunction "4_4") (pintype "passive"))
      (node (ref "SJ12") (pin "2") (pinfunction "2_2") (pintype "passive"))
    )
    (net (code "77") (name "/VBUS_A") (class "Default")
      (node (ref "JP1") (pin "4") (pinfunction "4_4") (pintype "passive"))
      (node (ref "SJ14") (pin "2") (pinfunction "2_2") (pintype "passive"))
    )
    (net (code "78") (name "/VCAP") (class "Default")
      (node (ref "C12") (pin "1") (pinfunction "1_1") (pintype "passive"))
      (node (ref "U$23") (pin "30") (pinfunction "30:VCAP_30") (pintype "bidirectional"))
    )
    (net (code "79") (name "/VCONN") (class "Default")
      (node (ref "JP2") (pin "6") (pinfunction "6_6") (pintype "passive"))
      (node (ref "SJ13") (pin "2") (pinfunction "2_2") (pintype "passive"))
    )
    (net (code "80") (name "/VCONNA") (class "Default")
      (node (ref "JP1") (pin "1") (pinfunction "1_1") (pintype "passive"))
      (node (ref "SJ9") (pin "1") (pinfunction "1_1") (pintype "passive"))
    )
    (net (code "81") (name "/VDD") (class "Default")
      (node (ref "JP1") (pin "12") (pinfunction "12_12") (pintype "passive"))
      (node (ref "SJ8") (pin "1") (pinfunction "1_1") (pintype "passive"))
    )
    (net (code "82") (name "/VLT_DIR") (class "Default")
      (node (ref "U$23") (pin "36") (pinfunction "PB15_36") (pintype "bidirectional"))
      (node (ref "U1") (pin "2") (pinfunction "DIR_2") (pintype "input"))
    )
    (net (code "83") (name "/VPU") (class "Default")
      (node (ref "JP1") (pin "11") (pinfunction "11_11") (pintype "passive"))
    )
    (net (code "84") (name "/V_PULLUP") (class "Default")
      (node (ref "JP1") (pin "2") (pinfunction "2_2") (pintype "passive"))
    )
    (net (code "85") (name "/WIFI_CS") (class "Default")
      (node (ref "U$23") (pin "28") (pinfunction "PB2_28") (pintype "bidirectional"))
      (node (ref "U$24") (pin "D8") (pinfunction "D8_D8") (pintype "bidirectional"))
    )
    (net (code "86") (name "/WIFI_GPIO") (class "Default")
      (node (ref "U$24") (pin "D1") (pinfunction "D1_D1") (pintype "bidirectional"))
    )
    (net (code "87") (name "/WIFI_IRQ") (class "Default")
      (node (ref "U$23") (pin "29") (pinfunction "PB10_29") (pintype "bidirectional"))
      (node (ref "U$24") (pin "D0") (pinfunction "D0_D0") (pintype "bidirectional"))
    )
    (net (code "88") (name "Net-(R6-Pad1)") (class "Default")
      (node (ref "R6") (pin "1") (pinfunction "1_1") (pintype "passive"))
      (node (ref "U$19") (pin "D") (pinfunction "D_D") (pintype "bidirectional"))
    )
    (net (code "89") (name "Net-(R6-Pad2)") (class "Default")
      (node (ref "R6") (pin "2") (pinfunction "2_2") (pintype "passive"))
      (node (ref "U$18") (pin "CATH") (pinfunction "CATH_CATH") (pintype "bidirectional"))
    )
    (net (code "90") (name "Net-(U$1-11)") (class "Default")
      (node (ref "JP6") (pin "3") (pinfunction "3_3") (pintype "passive"))
      (node (ref "U$1") (pin "P$11") (pinfunction "11_P$11") (pintype "passive"))
    )
    (net (code "91") (name "Net-(U$1-22)") (class "Default")
      (node (ref "JP6") (pin "1") (pinfunction "1_1") (pintype "passive"))
      (node (ref "U$1") (pin "P$22") (pinfunction "22_P$22") (pintype "passive"))
    )
    (net (code "92") (name "Net-(U$1-44)") (class "Default")
      (node (ref "JP6") (pin "2") (pinfunction "2_2") (pintype "passive"))
      (node (ref "U$1") (pin "P$44") (pinfunction "44_P$44") (pintype "passive"))
    )
    (net (code "93") (name "Net-(U$2-11)") (class "Default")
      (node (ref "JP6") (pin "17") (pinfunction "17_17") (pintype "passive"))
      (node (ref "U$2") (pin "P$11") (pinfunction "11_P$11") (pintype "passive"))
    )
    (net (code "94") (name "Net-(U$2-22)") (class "Default")
      (node (ref "JP6") (pin "15") (pinfunction "15_15") (pintype "passive"))
      (node (ref "U$2") (pin "P$22") (pinfunction "22_P$22") (pintype "passive"))
    )
    (net (code "95") (name "Net-(U$2-33)") (class "Default")
      (node (ref "JP6") (pin "16") (pinfunction "16_16") (pintype "passive"))
      (node (ref "U$2") (pin "P$33") (pinfunction "33_P$33") (pintype "passive"))
    )
    (net (code "96") (name "Net-(U$2-44)") (class "Default")
      (node (ref "JP6") (pin "18") (pinfunction "18_18") (pintype "passive"))
      (node (ref "U$2") (pin "P$44") (pinfunction "44_P$44") (pintype "passive"))
    )
    (net (code "97") (name "Net-(U$23-PH1)") (class "Default")
      (node (ref "R3") (pin "2") (pinfunction "2_2") (pintype "passive"))
      (node (ref "U$23") (pin "6") (pinfunction "PH1_6") (pintype "bidirectional"))
    )
    (net (code "98") (name "unconnected-(JP1-Pad3)") (class "Default")
      (node (ref "JP1") (pin "3") (pinfunction "3_3") (pintype "passive"))
    )
    (net (code "99") (name "unconnected-(JP6-Pad29)") (class "Default")
      (node (ref "JP6") (pin "29") (pinfunction "29_29") (pintype "passive"))
    )
    (net (code "100") (name "unconnected-(JP7-Pad6)") (class "Default")
      (node (ref "JP7") (pin "6") (pinfunction "6_6") (pintype "passive"))
    )
    (net (code "101") (name "unconnected-(JP8-Pad6)") (class "Default")
      (node (ref "JP8") (pin "6") (pinfunction "6_6") (pintype "passive"))
    )
    (net (code "102") (name "unconnected-(R2-E-Pad3)") (class "Default")
      (node (ref "R2") (pin "3") (pinfunction "E_3") (pintype "passive"))
    )
    (net (code "103") (name "unconnected-(U$4-4-PadP$4)") (class "Default")
      (node (ref "U$4") (pin "P$4") (pinfunction "4_P$4") (pintype "passive"))
    )
    (net (code "104") (name "unconnected-(U$4-44-PadP$44)") (class "Default")
      (node (ref "U$4") (pin "P$44") (pinfunction "44_P$44") (pintype "passive"))
    )
    (net (code "105") (name "unconnected-(U$23-PC15-Pad4)") (class "Default")
      (node (ref "U$23") (pin "4") (pinfunction "PC15_4") (pintype "bidirectional"))
    )
    (net (code "106") (name "unconnected-(U$24-PadA0)") (class "Default")
      (node (ref "U$24") (pin "A0") (pinfunction "A0_A0") (pintype "bidirectional"))
    )
    (net (code "107") (name "unconnected-(U$24-PadCLK)") (class "Default")
      (node (ref "U$24") (pin "CLK") (pinfunction "CLK_CLK") (pintype "bidirectional"))
    )
    (net (code "108") (name "unconnected-(U$24-PadCMD)") (class "Default")
      (node (ref "U$24") (pin "CMD") (pinfunction "CMD_CMD") (pintype "bidirectional"))
    )
    (net (code "109") (name "unconnected-(U$24-PadD2)") (class "Default")
      (node (ref "U$24") (pin "D2") (pinfunction "D2_D2") (pintype "bidirectional"))
    )
    (net (code "110") (name "unconnected-(U$24-PadD3)") (class "Default")
      (node (ref "U$24") (pin "D3") (pinfunction "D3_D3") (pintype "bidirectional"))
    )
    (net (code "111") (name "unconnected-(U$24-PadD4)") (class "Default")
      (node (ref "U$24") (pin "D4") (pinfunction "D4_D4") (pintype "bidirectional"))
    )
    (net (code "112") (name "unconnected-(U$24-PadEN)") (class "Default")
      (node (ref "U$24") (pin "EN") (pinfunction "EN_EN") (pintype "bidirectional"))
    )
    (net (code "113") (name "unconnected-(U$24-PadRST)") (class "Default")
      (node (ref "U$24") (pin "RST") (pinfunction "RST_RST") (pintype "bidirectional"))
    )
    (net (code "114") (name "unconnected-(U$24-PadRSV)") (class "Default")
      (node (ref "U$24") (pin "RSV") (pinfunction "RSV_RSV") (pintype "bidirectional"))
    )
    (net (code "115") (name "unconnected-(U$24-PadRX)") (class "Default")
      (node (ref "U$24") (pin "RX") (pinfunction "RX_RX") (pintype "bidirectional"))
    )
    (net (code "116") (name "unconnected-(U$24-PadSD0)") (class "Default")
      (node (ref "U$24") (pin "SD0") (pinfunction "SD0_SD0") (pintype "bidirectional"))
    )
    (net (code "117") (name "unconnected-(U$24-PadSD1)") (class "Default")
      (node (ref "U$24") (pin "SD1") (pinfunction "SD1_SD1") (pintype "bidirectional"))
    )
    (net (code "118") (name "unconnected-(U$24-PadSD2)") (class "Default")
      (node (ref "U$24") (pin "SD2") (pinfunction "SD2_SD2") (pintype "bidirectional"))
    )
    (net (code "119") (name "unconnected-(U$24-PadSD3)") (class "Default")
      (node (ref "U$24") (pin "SD3") (pinfunction "SD3_SD3") (pintype "bidirectional"))
    )
    (net (code "120") (name "unconnected-(U$24-PadTX)") (class "Default")
      (node (ref "U$24") (pin "TX") (pinfunction "TX_TX") (pintype "bidirectional"))
    )
    (net (code "121") (name "unconnected-(U$24-RSV-PadRSV@1)") (class "Default")
      (node (ref "U$24") (pin "RSV@1") (pinfunction "RSV_RSV@1") (pintype "bidirectional"))
    )
    (net (code "122") (name "unconnected-(U1-A6-Pad9)") (class "Default")
      (node (ref "U1") (pin "9") (pinfunction "A6_9") (pintype "bidirectional"))
    )
    (net (code "123") (name "unconnected-(U1-A7-Pad10)") (class "Default")
      (node (ref "U1") (pin "10") (pinfunction "A7_10") (pintype "bidirectional"))
    )
    (net (code "124") (name "unconnected-(U1-B6-Pad15)") (class "Default")
      (node (ref "U1") (pin "15") (pinfunction "B6_15") (pintype "bidirectional"))
    )
    (net (code "125") (name "unconnected-(U1-B7-Pad14)") (class "Default")
      (node (ref "U1") (pin "14") (pinfunction "B7_14") (pintype "bidirectional"))
    )
  )
)
